# dabl_card_reader.net
KiCad netlist of a schematic drawn in EAGLE
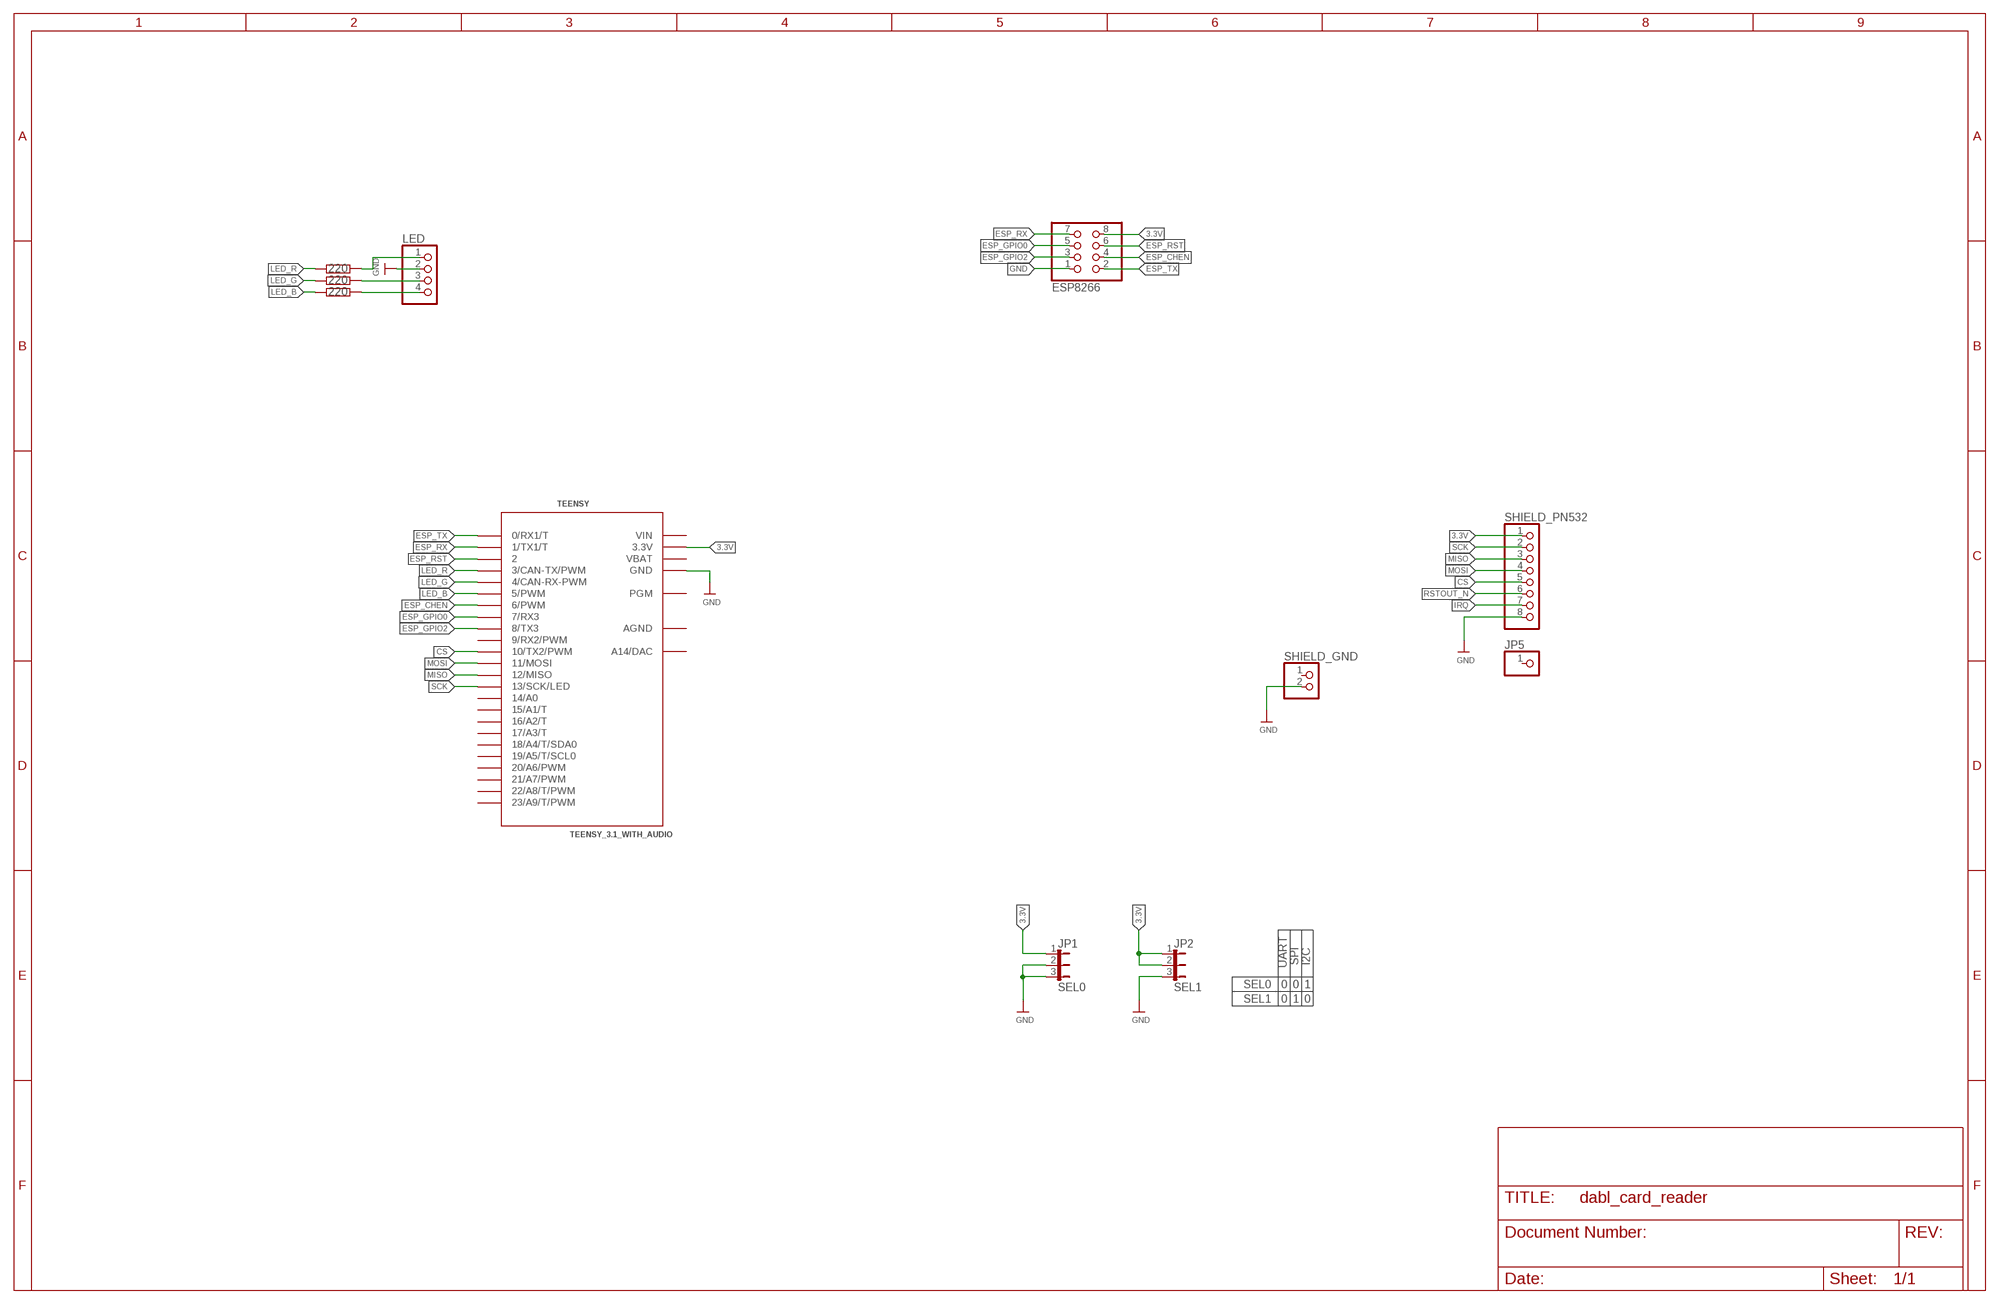
[diagram p0: schematic, sheet 1]

(export (version "E")
  (design (tool "Eeschema 10.0.6"))
  (components
    (comp (ref "ESP8266")
      (value "PINHD-2X4")
      (footprint "eagle-import:2X04")
      (libsource (lib "eagle-import") (part "PINHD-2X4"))
    )
    (comp (ref "JP1")
      (value "SEL0")
      (footprint "eagle-import:JUMPER3")
      (libsource (lib "eagle-import") (part "JUMPER3"))
    )
    (comp (ref "JP2")
      (value "SEL1")
      (footprint "eagle-import:JUMPER3")
      (libsource (lib "eagle-import") (part "JUMPER3"))
    )
    (comp (ref "JP5")
      (value "HEADER-1X1ROUND")
      (footprint "eagle-import:1X01_ROUND")
      (libsource (lib "eagle-import") (part "HEADER-1X1ROUND"))
    )
    (comp (ref "LED")
      (value "PINHD-1X4")
      (footprint "eagle-import:1X04")
      (libsource (lib "eagle-import") (part "PINHD-1X4"))
    )
    (comp (ref "R1")
      (value "220")
      (footprint "eagle-import:M0805")
      (libsource (lib "eagle-import") (part "R-EU_M0805"))
    )
    (comp (ref "R2")
      (value "220")
      (footprint "eagle-import:M0805")
      (libsource (lib "eagle-import") (part "R-EU_M0805"))
    )
    (comp (ref "R3")
      (value "220")
      (footprint "eagle-import:M0805")
      (libsource (lib "eagle-import") (part "R-EU_M0805"))
    )
    (comp (ref "SHIELD_GND")
      (value "PINHD-1X2")
      (footprint "eagle-import:1X02")
      (libsource (lib "eagle-import") (part "PINHD-1X2"))
    )
    (comp (ref "SHIELD_PN532")
      (value "HEADER-1X8ROUND")
      (footprint "eagle-import:1X08_ROUND")
      (libsource (lib "eagle-import") (part "HEADER-1X8ROUND"))
    )
    (comp (ref "TEENSY")
      (value "TEENSY_3.1_WITH_AUDIO")
      (footprint "eagle-import:TEENSY_3.2_WITH_AUDIO")
      (libsource (lib "eagle-import") (part "TEENSY_3.1_WITH_AUDIO"))
    )
  )
  (nets
    (net (code "1") (name "/AGND") (class "Default")
      (node (ref "TEENSY") (pin "AGND") (pinfunction "AGND_AGND") (pintype "power_in"))
    )
    (net (code "2") (name "/VBAT") (class "Default")
      (node (ref "TEENSY") (pin "VBAT") (pinfunction "VBAT_VBAT") (pintype "power_in"))
    )
    (net (code "3") (name "/VIN") (class "Default")
      (node (ref "TEENSY") (pin "VIN") (pinfunction "VIN_VIN") (pintype "power_in"))
    )
    (net (code "4") (name "3.3V") (class "Default")
      (node (ref "ESP8266") (pin "8") (pinfunction "8_8") (pintype "passive"))
      (node (ref "JP1") (pin "1") (pinfunction "1_1") (pintype "passive"))
      (node (ref "JP2") (pin "1") (pinfunction "1_1") (pintype "passive"))
      (node (ref "JP2") (pin "2") (pinfunction "2_2") (pintype "passive"))
      (node (ref "SHIELD_PN532") (pin "1") (pinfunction "1_1") (pintype "passive"))
      (node (ref "TEENSY") (pin "3.3V") (pinfunction "3.3V_3.3V") (pintype "power_in"))
      (node (ref "TEENSY") (pin "3.3V1") (pinfunction "3.3V_3.3V1") (pintype "power_in"))
    )
    (net (code "5") (name "CS") (class "Default")
      (node (ref "SHIELD_PN532") (pin "5") (pinfunction "5_5") (pintype "passive"))
      (node (ref "TEENSY") (pin "10") (pinfunction "10/TX2/PWM_10") (pintype "bidirectional"))
    )
    (net (code "6") (name "ESP_CHEN") (class "Default")
      (node (ref "ESP8266") (pin "4") (pinfunction "4_4") (pintype "passive"))
      (node (ref "TEENSY") (pin "6") (pinfunction "6/PWM_6") (pintype "bidirectional"))
    )
    (net (code "7") (name "ESP_GPIO0") (class "Default")
      (node (ref "ESP8266") (pin "5") (pinfunction "5_5") (pintype "passive"))
      (node (ref "TEENSY") (pin "7") (pinfunction "7/RX3_7") (pintype "bidirectional"))
    )
    (net (code "8") (name "ESP_GPIO2") (class "Default")
      (node (ref "ESP8266") (pin "3") (pinfunction "3_3") (pintype "passive"))
      (node (ref "TEENSY") (pin "8") (pinfunction "8/TX3_8") (pintype "bidirectional"))
    )
    (net (code "9") (name "ESP_RST") (class "Default")
      (node (ref "ESP8266") (pin "6") (pinfunction "6_6") (pintype "passive"))
      (node (ref "TEENSY") (pin "2") (pinfunction "2_2") (pintype "bidirectional"))
    )
    (net (code "10") (name "ESP_RX") (class "Default")
      (node (ref "ESP8266") (pin "7") (pinfunction "7_7") (pintype "passive"))
      (node (ref "TEENSY") (pin "1") (pinfunction "1/TX1/T_1") (pintype "bidirectional"))
    )
    (net (code "11") (name "ESP_TX") (class "Default")
      (node (ref "ESP8266") (pin "2") (pinfunction "2_2") (pintype "passive"))
      (node (ref "TEENSY") (pin "0") (pinfunction "0/RX1/T_0") (pintype "bidirectional"))
    )
    (net (code "12") (name "GND") (class "Default")
      (node (ref "ESP8266") (pin "1") (pinfunction "1_1") (pintype "passive"))
      (node (ref "JP1") (pin "2") (pinfunction "2_2") (pintype "passive"))
      (node (ref "JP1") (pin "3") (pinfunction "3_3") (pintype "passive"))
      (node (ref "JP2") (pin "3") (pinfunction "3_3") (pintype "passive"))
      (node (ref "LED") (pin "2") (pinfunction "2_2") (pintype "passive"))
      (node (ref "SHIELD_GND") (pin "2") (pinfunction "2_2") (pintype "passive"))
      (node (ref "SHIELD_PN532") (pin "8") (pinfunction "8_8") (pintype "passive"))
      (node (ref "TEENSY") (pin "GND") (pinfunction "GND_GND") (pintype "power_in"))
      (node (ref "TEENSY") (pin "GND1") (pinfunction "GND_GND1") (pintype "power_in"))
    )
    (net (code "13") (name "IRQ") (class "Default")
      (node (ref "SHIELD_PN532") (pin "7") (pinfunction "7_7") (pintype "passive"))
    )
    (net (code "14") (name "LED_B") (class "Default")
      (node (ref "R3") (pin "2") (pinfunction "2_2") (pintype "passive"))
      (node (ref "TEENSY") (pin "5") (pinfunction "5/PWM_5") (pintype "bidirectional"))
    )
    (net (code "15") (name "LED_G") (class "Default")
      (node (ref "R2") (pin "2") (pinfunction "2_2") (pintype "passive"))
      (node (ref "TEENSY") (pin "4") (pinfunction "4/CAN-RX-PWM_4") (pintype "bidirectional"))
    )
    (net (code "16") (name "LED_R") (class "Default")
      (node (ref "R1") (pin "2") (pinfunction "2_2") (pintype "passive"))
      (node (ref "TEENSY") (pin "3") (pinfunction "3/CAN-TX/PWM_3") (pintype "bidirectional"))
    )
    (net (code "17") (name "MISO") (class "Default")
      (node (ref "SHIELD_PN532") (pin "3") (pinfunction "3_3") (pintype "passive"))
      (node (ref "TEENSY") (pin "12") (pinfunction "12/MISO_12") (pintype "bidirectional"))
    )
    (net (code "18") (name "MOSI") (class "Default")
      (node (ref "SHIELD_PN532") (pin "4") (pinfunction "4_4") (pintype "passive"))
      (node (ref "TEENSY") (pin "11") (pinfunction "11/MOSI_11") (pintype "bidirectional"))
    )
    (net (code "19") (name "Net-(LED-Pad1)") (class "Default")
      (node (ref "LED") (pin "1") (pinfunction "1_1") (pintype "passive"))
      (node (ref "R1") (pin "1") (pinfunction "1_1") (pintype "passive"))
    )
    (net (code "20") (name "Net-(LED-Pad3)") (class "Default")
      (node (ref "LED") (pin "3") (pinfunction "3_3") (pintype "passive"))
      (node (ref "R2") (pin "1") (pinfunction "1_1") (pintype "passive"))
    )
    (net (code "21") (name "Net-(LED-Pad4)") (class "Default")
      (node (ref "LED") (pin "4") (pinfunction "4_4") (pintype "passive"))
      (node (ref "R3") (pin "1") (pinfunction "1_1") (pintype "passive"))
    )
    (net (code "22") (name "RSTOUT_N") (class "Default")
      (node (ref "SHIELD_PN532") (pin "6") (pinfunction "6_6") (pintype "passive"))
    )
    (net (code "23") (name "SCK") (class "Default")
      (node (ref "SHIELD_PN532") (pin "2") (pinfunction "2_2") (pintype "passive"))
      (node (ref "TEENSY") (pin "13") (pinfunction "13/SCK/LED_13") (pintype "bidirectional"))
    )
    (net (code "24") (name "unconnected-(JP5-Pad1)") (class "Default")
      (node (ref "JP5") (pin "1") (pinfunction "1_1") (pintype "passive"))
    )
    (net (code "25") (name "unconnected-(SHIELD_GND-Pad1)") (class "Default")
      (node (ref "SHIELD_GND") (pin "1") (pinfunction "1_1") (pintype "passive"))
    )
    (net (code "26") (name "unconnected-(TEENSY-9{slash}RX2{slash}PWM-Pad9)") (class "Default")
      (node (ref "TEENSY") (pin "9") (pinfunction "9/RX2/PWM_9") (pintype "bidirectional"))
    )
    (net (code "27") (name "unconnected-(TEENSY-15{slash}A1{slash}T-Pad15{slash}A1)") (class "Default")
      (node (ref "TEENSY") (pin "15/A1") (pinfunction "15/A1/T_15/A1") (pintype "bidirectional"))
    )
    (net (code "28") (name "unconnected-(TEENSY-16{slash}A2{slash}T-Pad16{slash}A2)") (class "Default")
      (node (ref "TEENSY") (pin "16/A2") (pinfunction "16/A2/T_16/A2") (pintype "bidirectional"))
    )
    (net (code "29") (name "unconnected-(TEENSY-17{slash}A3{slash}T-Pad17{slash}A3)") (class "Default")
      (node (ref "TEENSY") (pin "17/A3") (pinfunction "17/A3/T_17/A3") (pintype "bidirectional"))
    )
    (net (code "30") (name "unconnected-(TEENSY-18{slash}A4{slash}T{slash}SDA0-Pad18{slash}A4)") (class "Default")
      (node (ref "TEENSY") (pin "18/A4") (pinfunction "18/A4/T/SDA0_18/A4") (pintype "bidirectional"))
    )
    (net (code "31") (name "unconnected-(TEENSY-19{slash}A5{slash}T{slash}SCL0-Pad19{slash}A5)") (class "Default")
      (node (ref "TEENSY") (pin "19/A5") (pinfunction "19/A5/T/SCL0_19/A5") (pintype "bidirectional"))
    )
    (net (code "32") (name "unconnected-(TEENSY-20{slash}A6{slash}PWM-Pad20{slash}A6)") (class "Default")
      (node (ref "TEENSY") (pin "20/A6") (pinfunction "20/A6/PWM_20/A6") (pintype "bidirectional"))
    )
    (net (code "33") (name "unconnected-(TEENSY-21{slash}A7{slash}PWM-Pad21{slash}A7)") (class "Default")
      (node (ref "TEENSY") (pin "21/A7") (pinfunction "21/A7/PWM_21/A7") (pintype "bidirectional"))
    )
    (net (code "34") (name "unconnected-(TEENSY-22{slash}A8{slash}T{slash}PWM-Pad22{slash}A8)") (class "Default")
      (node (ref "TEENSY") (pin "22/A8") (pinfunction "22/A8/T/PWM_22/A8") (pintype "bidirectional"))
    )
    (net (code "35") (name "unconnected-(TEENSY-23{slash}A9{slash}T{slash}PWM-Pad23{slash}A9)") (class "Default")
      (node (ref "TEENSY") (pin "23/A9") (pinfunction "23/A9/T/PWM_23/A9") (pintype "bidirectional"))
    )
    (net (code "36") (name "unconnected-(TEENSY-A14{slash}DAC-PadA14)") (class "Default")
      (node (ref "TEENSY") (pin "A14") (pinfunction "A14/DAC_A14") (pintype "bidirectional"))
    )
    (net (code "37") (name "unconnected-(TEENSY-Pad14{slash}A0)") (class "Default")
      (node (ref "TEENSY") (pin "14/A0") (pinfunction "14/A0_14/A0") (pintype "bidirectional"))
    )
    (net (code "38") (name "unconnected-(TEENSY-PadPGM)") (class "Default")
      (node (ref "TEENSY") (pin "PGM") (pinfunction "PGM_PGM") (pintype "bidirectional"))
    )
  )
)
